# Haptic_Sleeve_Schematic_Copy2.net
KiCad netlist of a schematic drawn in EAGLE
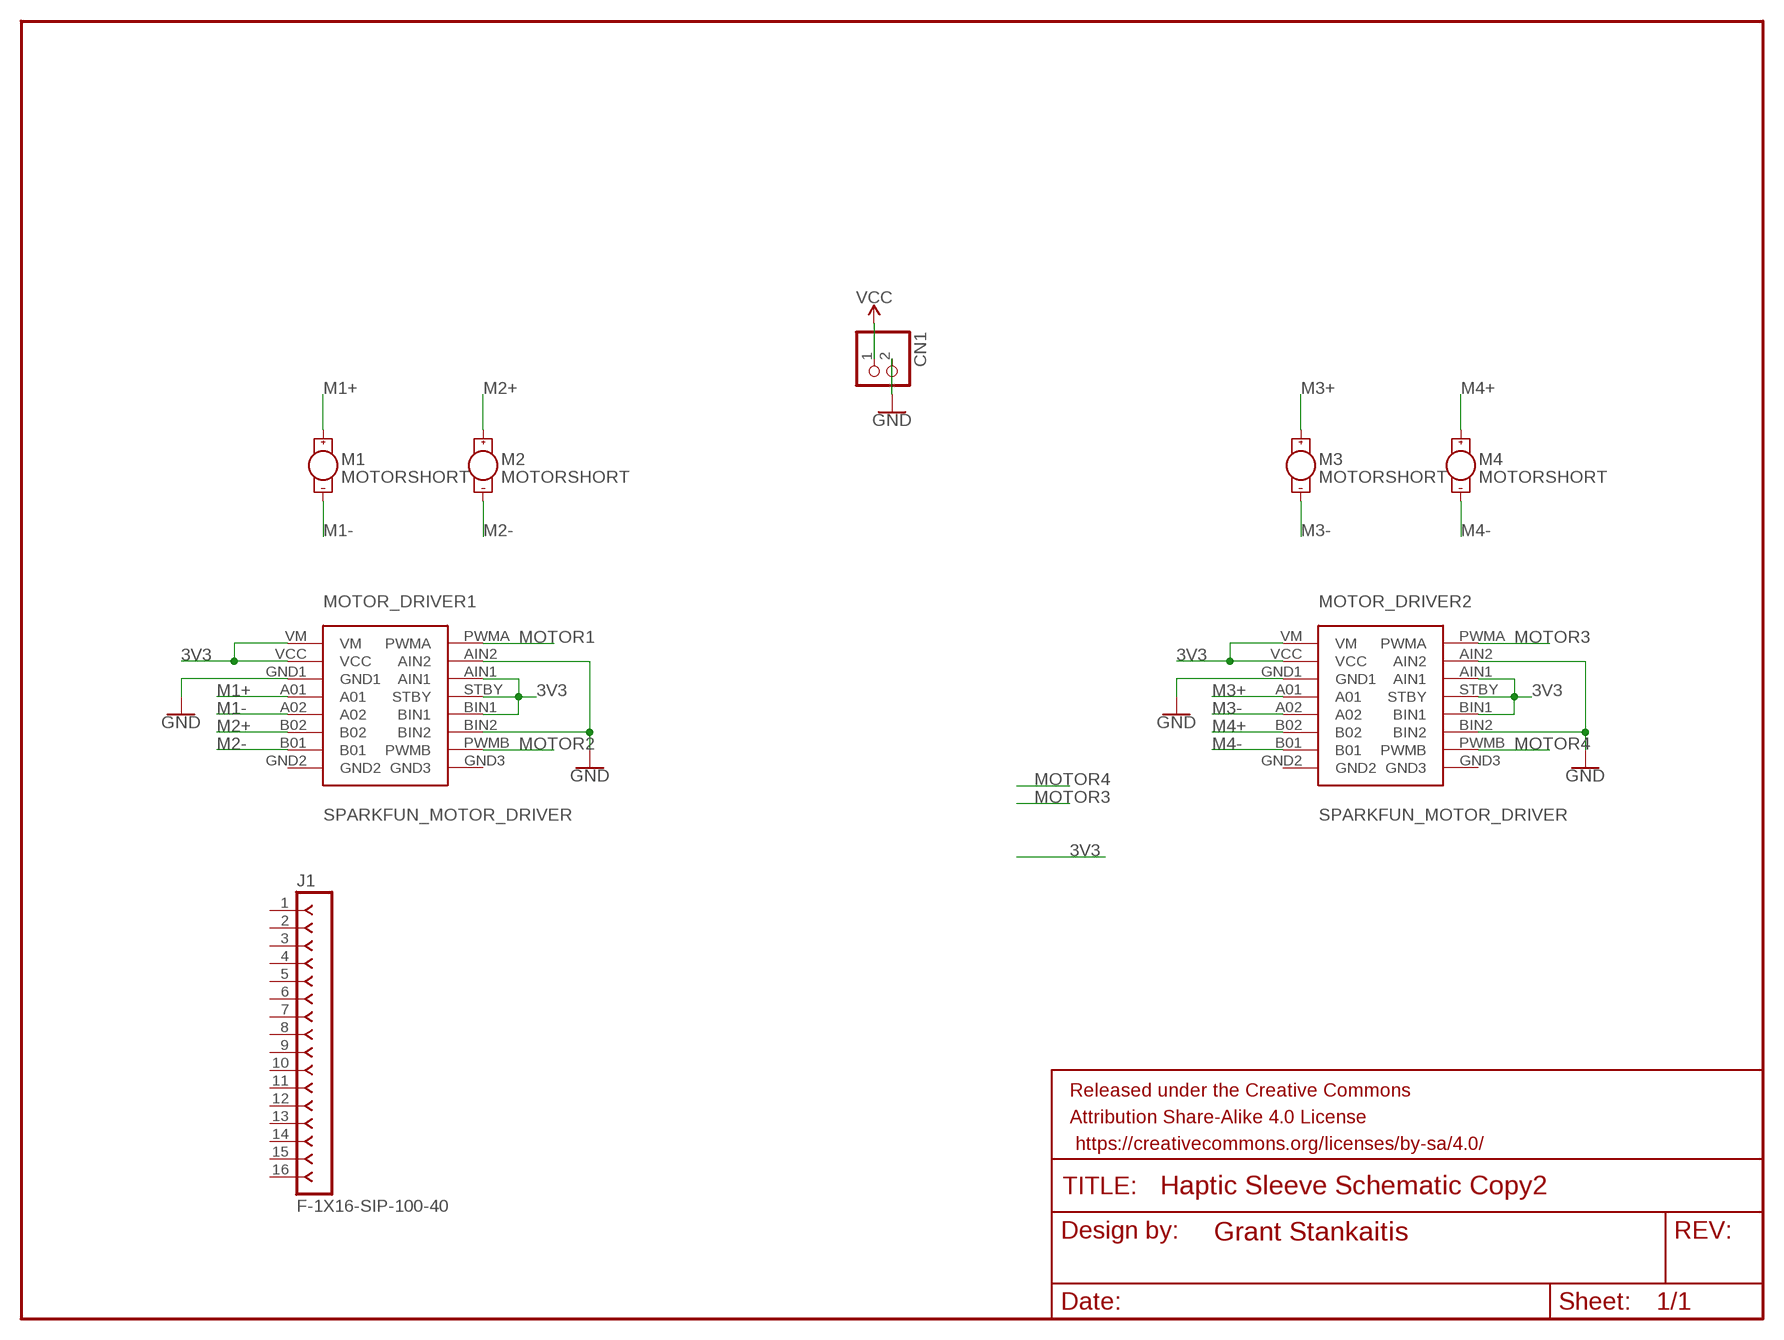
[diagram p0: schematic, sheet 1]

(export (version "E")
  (design (tool "Eeschema 10.0.6"))
  (components
    (comp (ref "CN1")
      (value "JST_2PIN-THM-RA")
      (footprint "eagle-import:JST-PH-2-THM-RA")
      (libsource (lib "eagle-import") (part "JST_2PIN-THM-RA"))
    )
    (comp (ref "FRAME1")
      (value "FRAME-LETTERNO_PACKAGE")
      (footprint "eagle-import:DUMMY")
      (fields (field (name "DESIGNER") "Nobody") (field (name "DESIGNER_1") "Grant Stankaitis"))
      (libsource (lib "eagle-import") (part "FRAME-LETTERNO_PACKAGE"))
    )
    (comp (ref "J1")
      (value "F-1X16-SIP-100-40")
      (footprint "eagle-import:SIP-100-16-40")
      (libsource (lib "eagle-import") (part "F-1X16-SIP-100-40"))
    )
    (comp (ref "M1")
      (value "MOTORSHORT")
      (footprint "eagle-import:VIBE-MOTOR-10MM-SMD")
      (libsource (lib "eagle-import") (part "MOTORSHORT"))
    )
    (comp (ref "M2")
      (value "MOTORSHORT")
      (footprint "eagle-import:VIBE-MOTOR-10MM-SMD")
      (libsource (lib "eagle-import") (part "MOTORSHORT"))
    )
    (comp (ref "M3")
      (value "MOTORSHORT")
      (footprint "eagle-import:VIBE-MOTOR-10MM-SMD")
      (libsource (lib "eagle-import") (part "MOTORSHORT"))
    )
    (comp (ref "M4")
      (value "MOTORSHORT")
      (footprint "eagle-import:VIBE-MOTOR-10MM-SMD")
      (libsource (lib "eagle-import") (part "MOTORSHORT"))
    )
    (comp (ref "MOTOR_DRIVER1")
      (value "SPARKFUN_MOTOR_DRIVER")
      (footprint "eagle-import:SPARKFUN_MOTOR_DRIVER")
      (libsource (lib "eagle-import") (part "SPARKFUN_MOTOR_DRIVER"))
    )
    (comp (ref "MOTOR_DRIVER2")
      (value "SPARKFUN_MOTOR_DRIVER")
      (footprint "eagle-import:SPARKFUN_MOTOR_DRIVER")
      (libsource (lib "eagle-import") (part "SPARKFUN_MOTOR_DRIVER"))
    )
  )
  (nets
    (net (code "1") (name "/3V3") (class "Default")
      (node (ref "MOTOR_DRIVER1") (pin "AIN1") (pinfunction "AIN1_AIN1") (pintype "bidirectional"))
      (node (ref "MOTOR_DRIVER1") (pin "BIN1") (pinfunction "BIN1_BIN1") (pintype "bidirectional"))
      (node (ref "MOTOR_DRIVER1") (pin "STBY") (pinfunction "STBY_STBY") (pintype "bidirectional"))
      (node (ref "MOTOR_DRIVER1") (pin "VCC") (pinfunction "VCC_VCC") (pintype "bidirectional"))
      (node (ref "MOTOR_DRIVER1") (pin "VM") (pinfunction "VM_VM") (pintype "bidirectional"))
      (node (ref "MOTOR_DRIVER2") (pin "AIN1") (pinfunction "AIN1_AIN1") (pintype "bidirectional"))
      (node (ref "MOTOR_DRIVER2") (pin "BIN1") (pinfunction "BIN1_BIN1") (pintype "bidirectional"))
      (node (ref "MOTOR_DRIVER2") (pin "STBY") (pinfunction "STBY_STBY") (pintype "bidirectional"))
      (node (ref "MOTOR_DRIVER2") (pin "VCC") (pinfunction "VCC_VCC") (pintype "bidirectional"))
      (node (ref "MOTOR_DRIVER2") (pin "VM") (pinfunction "VM_VM") (pintype "bidirectional"))
    )
    (net (code "2") (name "/M1+") (class "Default")
      (node (ref "M1") (pin "+") (pinfunction "+_+") (pintype "bidirectional"))
      (node (ref "MOTOR_DRIVER1") (pin "A01") (pinfunction "A01_A01") (pintype "bidirectional"))
    )
    (net (code "3") (name "/M1-") (class "Default")
      (node (ref "M1") (pin "-") (pinfunction "-_-") (pintype "bidirectional"))
      (node (ref "MOTOR_DRIVER1") (pin "A02") (pinfunction "A02_A02") (pintype "bidirectional"))
    )
    (net (code "4") (name "/M2+") (class "Default")
      (node (ref "M2") (pin "+") (pinfunction "+_+") (pintype "bidirectional"))
      (node (ref "MOTOR_DRIVER1") (pin "B02") (pinfunction "B02_B02") (pintype "bidirectional"))
    )
    (net (code "5") (name "/M2-") (class "Default")
      (node (ref "M2") (pin "-") (pinfunction "-_-") (pintype "bidirectional"))
      (node (ref "MOTOR_DRIVER1") (pin "B01") (pinfunction "B01_B01") (pintype "bidirectional"))
    )
    (net (code "6") (name "/M3+") (class "Default")
      (node (ref "M3") (pin "+") (pinfunction "+_+") (pintype "bidirectional"))
      (node (ref "MOTOR_DRIVER2") (pin "A01") (pinfunction "A01_A01") (pintype "bidirectional"))
    )
    (net (code "7") (name "/M3-") (class "Default")
      (node (ref "M3") (pin "-") (pinfunction "-_-") (pintype "bidirectional"))
      (node (ref "MOTOR_DRIVER2") (pin "A02") (pinfunction "A02_A02") (pintype "bidirectional"))
    )
    (net (code "8") (name "/M4+") (class "Default")
      (node (ref "M4") (pin "+") (pinfunction "+_+") (pintype "bidirectional"))
      (node (ref "MOTOR_DRIVER2") (pin "B02") (pinfunction "B02_B02") (pintype "bidirectional"))
    )
    (net (code "9") (name "/M4-") (class "Default")
      (node (ref "M4") (pin "-") (pinfunction "-_-") (pintype "bidirectional"))
      (node (ref "MOTOR_DRIVER2") (pin "B01") (pinfunction "B01_B01") (pintype "bidirectional"))
    )
    (net (code "10") (name "/MOTOR1") (class "Default")
      (node (ref "MOTOR_DRIVER1") (pin "PWMA") (pinfunction "PWMA_PWMA") (pintype "bidirectional"))
    )
    (net (code "11") (name "/MOTOR2") (class "Default")
      (node (ref "MOTOR_DRIVER1") (pin "PWMB") (pinfunction "PWMB_PWMB") (pintype "bidirectional"))
    )
    (net (code "12") (name "/MOTOR3") (class "Default")
      (node (ref "MOTOR_DRIVER2") (pin "PWMA") (pinfunction "PWMA_PWMA") (pintype "bidirectional"))
    )
    (net (code "13") (name "/MOTOR4") (class "Default")
      (node (ref "MOTOR_DRIVER2") (pin "PWMB") (pinfunction "PWMB_PWMB") (pintype "bidirectional"))
    )
    (net (code "14") (name "GND") (class "Default")
      (node (ref "CN1") (pin "2") (pinfunction "1_2") (pintype "passive"))
      (node (ref "MOTOR_DRIVER1") (pin "AIN2") (pinfunction "AIN2_AIN2") (pintype "bidirectional"))
      (node (ref "MOTOR_DRIVER1") (pin "BIN2") (pinfunction "BIN2_BIN2") (pintype "bidirectional"))
      (node (ref "MOTOR_DRIVER1") (pin "GND1") (pinfunction "GND1_GND1") (pintype "bidirectional"))
      (node (ref "MOTOR_DRIVER2") (pin "AIN2") (pinfunction "AIN2_AIN2") (pintype "bidirectional"))
      (node (ref "MOTOR_DRIVER2") (pin "BIN2") (pinfunction "BIN2_BIN2") (pintype "bidirectional"))
      (node (ref "MOTOR_DRIVER2") (pin "GND1") (pinfunction "GND1_GND1") (pintype "bidirectional"))
    )
    (net (code "15") (name "VCC") (class "Default")
      (node (ref "CN1") (pin "1") (pinfunction "2_1") (pintype "passive"))
    )
    (net (code "16") (name "unconnected-(J1-Pad1)") (class "Default")
      (node (ref "J1") (pin "1") (pinfunction "1_1") (pintype "passive"))
    )
    (net (code "17") (name "unconnected-(J1-Pad2)") (class "Default")
      (node (ref "J1") (pin "2") (pinfunction "2_2") (pintype "passive"))
    )
    (net (code "18") (name "unconnected-(J1-Pad3)") (class "Default")
      (node (ref "J1") (pin "3") (pinfunction "3_3") (pintype "passive"))
    )
    (net (code "19") (name "unconnected-(J1-Pad4)") (class "Default")
      (node (ref "J1") (pin "4") (pinfunction "4_4") (pintype "passive"))
    )
    (net (code "20") (name "unconnected-(J1-Pad5)") (class "Default")
      (node (ref "J1") (pin "5") (pinfunction "5_5") (pintype "passive"))
    )
    (net (code "21") (name "unconnected-(J1-Pad6)") (class "Default")
      (node (ref "J1") (pin "6") (pinfunction "6_6") (pintype "passive"))
    )
    (net (code "22") (name "unconnected-(J1-Pad7)") (class "Default")
      (node (ref "J1") (pin "7") (pinfunction "7_7") (pintype "passive"))
    )
    (net (code "23") (name "unconnected-(J1-Pad8)") (class "Default")
      (node (ref "J1") (pin "8") (pinfunction "8_8") (pintype "passive"))
    )
    (net (code "24") (name "unconnected-(J1-Pad9)") (class "Default")
      (node (ref "J1") (pin "9") (pinfunction "9_9") (pintype "passive"))
    )
    (net (code "25") (name "unconnected-(J1-Pad10)") (class "Default")
      (node (ref "J1") (pin "10") (pinfunction "10_10") (pintype "passive"))
    )
    (net (code "26") (name "unconnected-(J1-Pad11)") (class "Default")
      (node (ref "J1") (pin "11") (pinfunction "11_11") (pintype "passive"))
    )
    (net (code "27") (name "unconnected-(J1-Pad12)") (class "Default")
      (node (ref "J1") (pin "12") (pinfunction "12_12") (pintype "passive"))
    )
    (net (code "28") (name "unconnected-(J1-Pad13)") (class "Default")
      (node (ref "J1") (pin "13") (pinfunction "13_13") (pintype "passive"))
    )
    (net (code "29") (name "unconnected-(J1-Pad14)") (class "Default")
      (node (ref "J1") (pin "14") (pinfunction "14_14") (pintype "passive"))
    )
    (net (code "30") (name "unconnected-(J1-Pad15)") (class "Default")
      (node (ref "J1") (pin "15") (pinfunction "15_15") (pintype "passive"))
    )
    (net (code "31") (name "unconnected-(J1-Pad16)") (class "Default")
      (node (ref "J1") (pin "16") (pinfunction "16_16") (pintype "passive"))
    )
    (net (code "32") (name "unconnected-(MOTOR_DRIVER1-PadGND2)") (class "Default")
      (node (ref "MOTOR_DRIVER1") (pin "GND2") (pinfunction "GND2_GND2") (pintype "bidirectional"))
    )
    (net (code "33") (name "unconnected-(MOTOR_DRIVER1-PadGND3)") (class "Default")
      (node (ref "MOTOR_DRIVER1") (pin "GND3") (pinfunction "GND3_GND3") (pintype "bidirectional"))
    )
    (net (code "34") (name "unconnected-(MOTOR_DRIVER2-PadGND2)") (class "Default")
      (node (ref "MOTOR_DRIVER2") (pin "GND2") (pinfunction "GND2_GND2") (pintype "bidirectional"))
    )
    (net (code "35") (name "unconnected-(MOTOR_DRIVER2-PadGND3)") (class "Default")
      (node (ref "MOTOR_DRIVER2") (pin "GND3") (pinfunction "GND3_GND3") (pintype "bidirectional"))
    )
  )
)
